# Rasp.net
KiCad netlist of a schematic drawn in Altium Designer
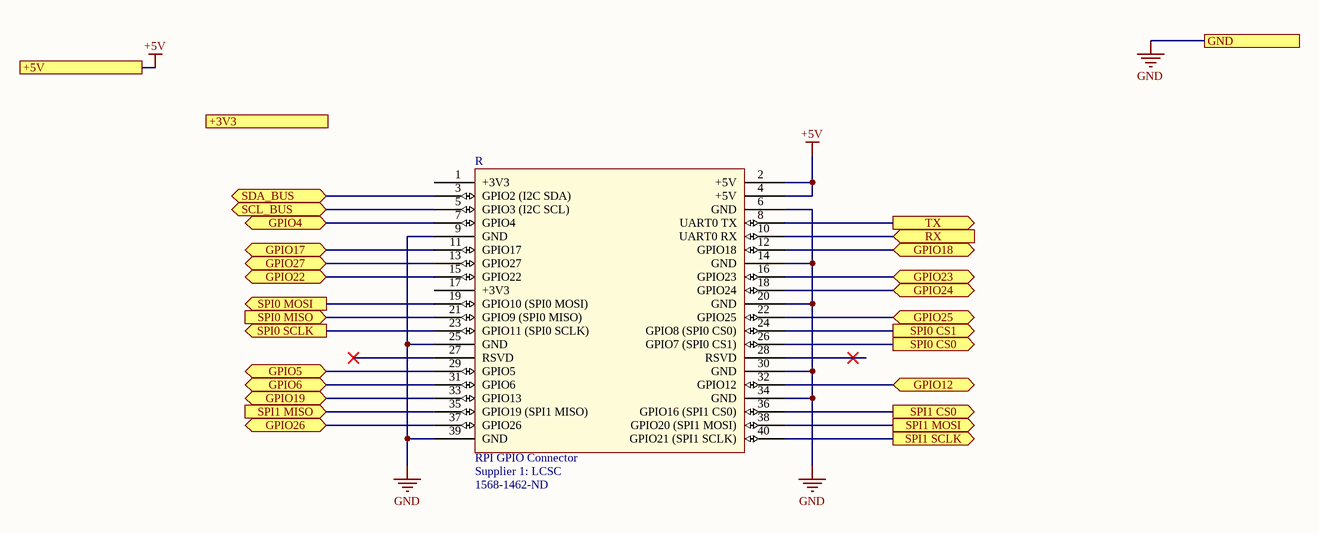
[diagram p0: Rasp.SchDoc]

(export (version "E")
  (design (tool "Eeschema 10.0.6"))
  (components
    (comp (ref "R")
      (value "RPI GPIO Connector")
      (footprint "rpi")
      (description "GPIO Header for Raspberry Pi A+/B+/Pi 2/Pi 3 - 2x20")
      (fields
        (field (name "MANUFACTURER") "SparkFun Electronics")
        (field (name "MANUFACTURER PART NUMBER") "PRT-14017")
        (field (name "SUPPLIER 1") "LCSC")
        (field (name "SUPPLIER PART NUMBER 1") "1568-1462-ND")
      )
      (libsource (lib "rpi") (part "rpi connector"))
    )
  )
  (nets
    (net (code "1") (name "+5V") (class "Default")
      (node (ref "R") (pin "2") (pinfunction "+5V_2") (pintype "power_in"))
      (node (ref "R") (pin "4") (pinfunction "+5V_4") (pintype "power_in"))
    )
    (net (code "3") (name "/GPIO4") (class "Default")
      (node (ref "R") (pin "7") (pinfunction "GPIO4_7") (pintype "bidirectional"))
    )
    (net (code "4") (name "/GPIO5") (class "Default")
      (node (ref "R") (pin "29") (pinfunction "GPIO5_29") (pintype "bidirectional"))
    )
    (net (code "5") (name "/GPIO6") (class "Default")
      (node (ref "R") (pin "31") (pinfunction "GPIO6_31") (pintype "bidirectional"))
    )
    (net (code "6") (name "/GPIO12") (class "Default")
      (node (ref "R") (pin "32") (pinfunction "GPIO12_32") (pintype "bidirectional"))
    )
    (net (code "7") (name "/GPIO17") (class "Default")
      (node (ref "R") (pin "11") (pinfunction "GPIO17_11") (pintype "bidirectional"))
    )
    (net (code "8") (name "/GPIO18") (class "Default")
      (node (ref "R") (pin "12") (pinfunction "GPIO18_12") (pintype "bidirectional"))
    )
    (net (code "9") (name "/GPIO19") (class "Default")
      (node (ref "R") (pin "33") (pinfunction "GPIO13_33") (pintype "bidirectional"))
    )
    (net (code "10") (name "/GPIO22") (class "Default")
      (node (ref "R") (pin "15") (pinfunction "GPIO22_15") (pintype "bidirectional"))
    )
    (net (code "11") (name "/GPIO23") (class "Default")
      (node (ref "R") (pin "16") (pinfunction "GPIO23_16") (pintype "bidirectional"))
    )
    (net (code "12") (name "/GPIO24") (class "Default")
      (node (ref "R") (pin "18") (pinfunction "GPIO24_18") (pintype "bidirectional"))
    )
    (net (code "13") (name "/GPIO25") (class "Default")
      (node (ref "R") (pin "22") (pinfunction "GPIO25_22") (pintype "bidirectional"))
    )
    (net (code "14") (name "/GPIO26") (class "Default")
      (node (ref "R") (pin "37") (pinfunction "GPIO26_37") (pintype "bidirectional"))
    )
    (net (code "15") (name "/GPIO27") (class "Default")
      (node (ref "R") (pin "13") (pinfunction "GPIO27_13") (pintype "bidirectional"))
    )
    (net (code "16") (name "/RX") (class "Default")
      (node (ref "R") (pin "10") (pinfunction "UART0_RX_10") (pintype "bidirectional"))
    )
    (net (code "17") (name "/SCL_BUS") (class "Default")
      (node (ref "R") (pin "5") (pinfunction "GPIO3_(I2C_SCL)_5") (pintype "bidirectional"))
    )
    (net (code "18") (name "/SDA_BUS") (class "Default")
      (node (ref "R") (pin "3") (pinfunction "GPIO2_(I2C_SDA)_3") (pintype "bidirectional"))
    )
    (net (code "19") (name "/SPI0 CS0") (class "Default")
      (node (ref "R") (pin "26") (pinfunction "GPIO7_(SPI0_CS1)_26") (pintype "bidirectional"))
    )
    (net (code "20") (name "/SPI0 CS1") (class "Default")
      (node (ref "R") (pin "24") (pinfunction "GPIO8_(SPI0_CS0)_24") (pintype "bidirectional"))
    )
    (net (code "21") (name "/SPI0 MISO") (class "Default")
      (node (ref "R") (pin "21") (pinfunction "GPIO9_(SPI0_MISO)_21") (pintype "bidirectional"))
    )
    (net (code "22") (name "/SPI0 MOSI") (class "Default")
      (node (ref "R") (pin "19") (pinfunction "GPIO10_(SPI0_MOSI)_19") (pintype "bidirectional"))
    )
    (net (code "23") (name "/SPI0 SCLK") (class "Default")
      (node (ref "R") (pin "23") (pinfunction "GPIO11_(SPI0_SCLK)_23") (pintype "bidirectional"))
    )
    (net (code "24") (name "/SPI1 CS0") (class "Default")
      (node (ref "R") (pin "36") (pinfunction "GPIO16_(SPI1_CS0)_36") (pintype "bidirectional"))
    )
    (net (code "25") (name "/SPI1 MISO") (class "Default")
      (node (ref "R") (pin "35") (pinfunction "GPIO19_(SPI1_MISO)_35") (pintype "bidirectional"))
    )
    (net (code "26") (name "/SPI1 MOSI") (class "Default")
      (node (ref "R") (pin "38") (pinfunction "GPIO20_(SPI1_MOSI)_38") (pintype "bidirectional"))
    )
    (net (code "27") (name "/SPI1 SCLK") (class "Default")
      (node (ref "R") (pin "40") (pinfunction "GPIO21_(SPI1_SCLK)_40") (pintype "bidirectional"))
    )
    (net (code "28") (name "/TX") (class "Default")
      (node (ref "R") (pin "8") (pinfunction "UART0_TX_8") (pintype "bidirectional"))
    )
    (net (code "29") (name "GND") (class "Default")
      (node (ref "R") (pin "14") (pinfunction "GND_14") (pintype "power_in"))
      (node (ref "R") (pin "20") (pinfunction "GND_20") (pintype "power_in"))
      (node (ref "R") (pin "25") (pinfunction "GND_25") (pintype "power_in"))
      (node (ref "R") (pin "30") (pinfunction "GND_30") (pintype "power_in"))
      (node (ref "R") (pin "34") (pinfunction "GND_34") (pintype "passive"))
      (node (ref "R") (pin "39") (pinfunction "GND_39") (pintype "power_in"))
      (node (ref "R") (pin "6") (pinfunction "GND_6") (pintype "power_in"))
      (node (ref "R") (pin "9") (pinfunction "GND_9") (pintype "power_in"))
    )
    (net (code "30") (name "unconnected-(R-+3V3-Pad1)") (class "Default")
      (node (ref "R") (pin "1") (pinfunction "+3V3_1") (pintype "power_in"))
    )
    (net (code "31") (name "unconnected-(R-+3V3-Pad17)") (class "Default")
      (node (ref "R") (pin "17") (pinfunction "+3V3_17") (pintype "power_in"))
    )
    (net (code "32") (name "unconnected-(R-RSVD-Pad27)") (class "Default")
      (node (ref "R") (pin "27") (pinfunction "RSVD_27") (pintype "passive+no_connect"))
    )
    (net (code "33") (name "unconnected-(R-RSVD-Pad28)") (class "Default")
      (node (ref "R") (pin "28") (pinfunction "RSVD_28") (pintype "passive"))
    )
  )
)
